# Mako_DSP_Power_R1_3.net
KiCad netlist of a schematic drawn in Altium Designer
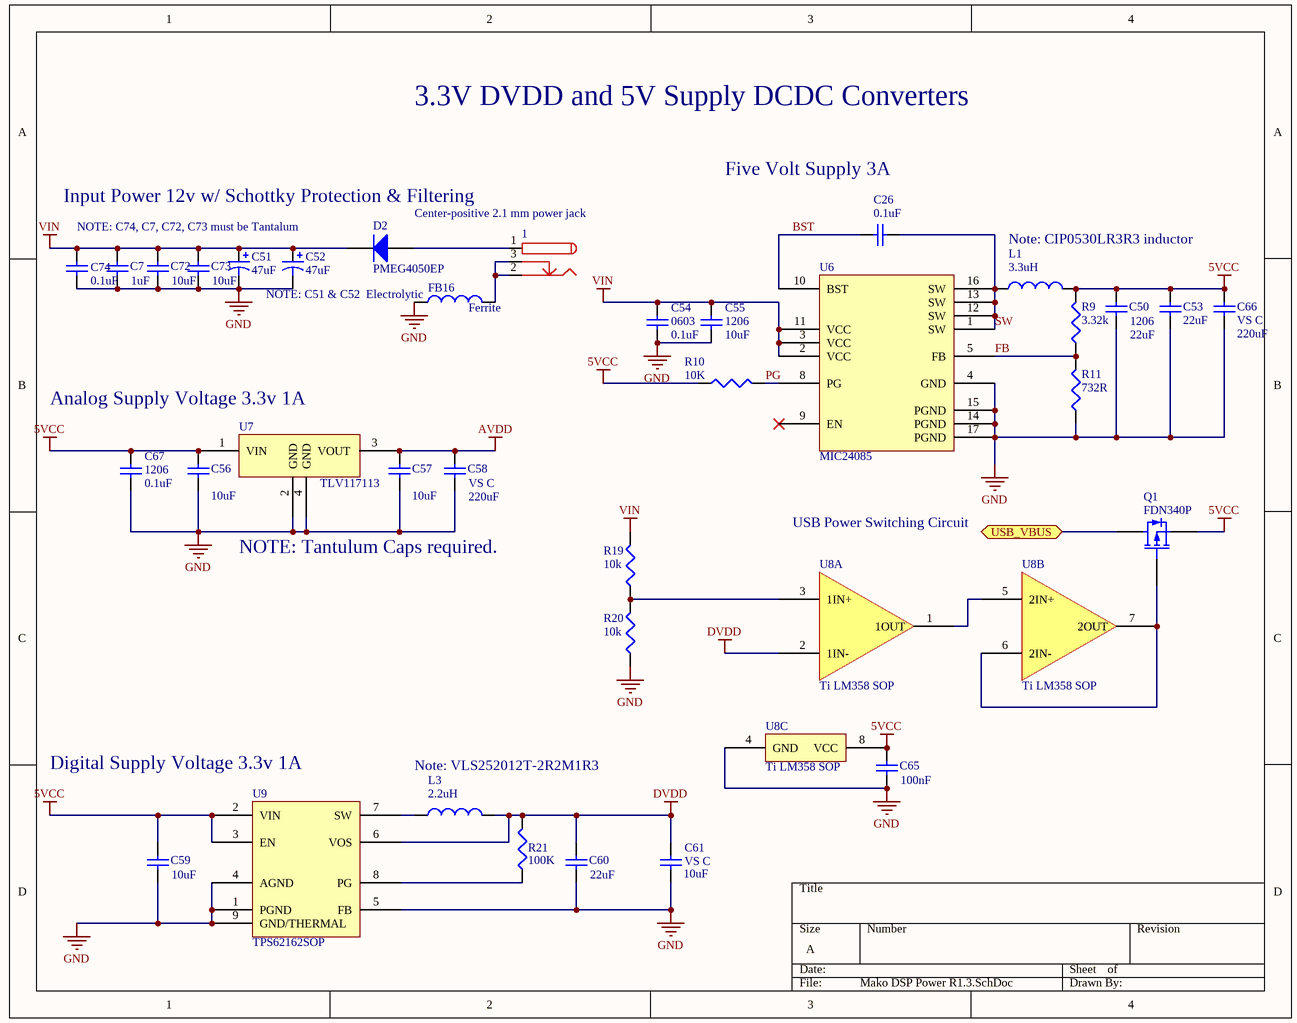
[diagram p0: Mako DSP Power R1.3.SchDoc]

(export (version "E")
  (design (tool "Eeschema 10.0.6"))
  (components
    (comp (ref "1")
      (value "Center-positive 2.1 mm power jack")
      (footprint "PJ-102AH")
      (description "Power jack")
      (fields (field (name "PUBLISHER") "Altium Limited"))
      (libsource (lib "Rascal") (part "PWR2.5"))
    )
    (comp (ref "C7")
      (value "1uF")
      (footprint "C1206")
      (description "Capacitor (Semiconductor SIM Model)")
      (fields (field (name "Comment") "Cap Semi") (field (name "PUBLISHER") "Altium Limited"))
      (libsource (lib "Miscellaneous Devices") (part "Cap Semi"))
    )
    (comp (ref "C26")
      (value "0.1uF")
      (footprint "1608[0603]")
      (description "Capacitor (Semiconductor SIM Model)")
      (fields (field (name "Comment") "Cap Semi") (field (name "PUBLISHER") "Altium Limited"))
      (libsource (lib "Miscellaneous Devices") (part "Cap Semi"))
    )
    (comp (ref "C50")
      (value "1206")
      (footprint "C1206")
      (description "Capacitor (Semiconductor SIM Model)")
      (fields (field (name "ALTIUM_VALUE") "22uF") (field (name "PUBLISHER") "Altium Limited"))
      (libsource (lib "Miscellaneous Devices") (part "Cap Semi"))
    )
    (comp (ref "C51")
      (value "47uF")
      (footprint "CAPPR2.5-6.3x5")
      (description "Polarized Capacitor (Radial)")
      (fields (field (name "Comment") "Cap Pol1") (field (name "PUBLISHER") "Altium Limited"))
      (libsource (lib "Miscellaneous Devices") (part "Cap Pol1"))
    )
    (comp (ref "C52")
      (value "47uF")
      (footprint "CAPPR2.5-6.3x5")
      (description "Polarized Capacitor (Radial)")
      (fields (field (name "Comment") "Cap Pol1") (field (name "PUBLISHER") "Altium Limited"))
      (libsource (lib "Miscellaneous Devices") (part "Cap Pol1"))
    )
    (comp (ref "C53")
      (value "22uF")
      (footprint "C1206")
      (description "Capacitor (Semiconductor SIM Model)")
      (fields (field (name "Comment") "Cap Semi") (field (name "PUBLISHER") "Altium Limited"))
      (libsource (lib "Miscellaneous Devices") (part "Cap Semi"))
    )
    (comp (ref "C54")
      (value "0603")
      (footprint "1608[0603]")
      (description "Capacitor (Semiconductor SIM Model)")
      (fields (field (name "ALTIUM_VALUE") "0.1uF") (field (name "PUBLISHER") "Altium Limited"))
      (libsource (lib "Miscellaneous Devices") (part "Cap Semi"))
    )
    (comp (ref "C55")
      (value "1206")
      (footprint "C1206")
      (description "Capacitor (Semiconductor SIM Model)")
      (fields (field (name "ALTIUM_VALUE") "10uF") (field (name "PUBLISHER") "Altium Limited"))
      (libsource (lib "Miscellaneous Devices") (part "Cap Semi"))
    )
    (comp (ref "C56")
      (value "10uF")
      (footprint "C1206")
      (description "Capacitor (Semiconductor SIM Model)")
      (fields (field (name "Comment") "Cap Semi") (field (name "PUBLISHER") "Altium Limited"))
      (libsource (lib "Miscellaneous Devices") (part "Cap Semi"))
    )
    (comp (ref "C57")
      (value "10uF")
      (footprint "C1206")
      (description "Capacitor (Semiconductor SIM Model)")
      (fields (field (name "Comment") "Cap Semi") (field (name "PUBLISHER") "Altium Limited"))
      (libsource (lib "Miscellaneous Devices") (part "Cap Semi"))
    )
    (comp (ref "C58")
      (value "VS C")
      (footprint "Panasonic VS C")
      (description "Capacitor (Semiconductor SIM Model)")
      (fields (field (name "ALTIUM_VALUE") "220uF") (field (name "PUBLISHER") "Altium Limited"))
      (libsource (lib "Miscellaneous Devices") (part "Cap Semi"))
    )
    (comp (ref "C59")
      (value "10uF")
      (footprint "C1206")
      (description "Capacitor (Semiconductor SIM Model)")
      (fields (field (name "Comment") "Cap Semi") (field (name "PUBLISHER") "Altium Limited"))
      (libsource (lib "Miscellaneous Devices") (part "Cap Semi"))
    )
    (comp (ref "C60")
      (value "22uF")
      (footprint "C1206")
      (description "Capacitor (Semiconductor SIM Model)")
      (fields (field (name "Comment") "Cap Semi") (field (name "PUBLISHER") "Altium Limited"))
      (libsource (lib "Miscellaneous Devices") (part "Cap Semi"))
    )
    (comp (ref "C61")
      (value "VS C")
      (footprint "Panasonic VS C")
      (description "Capacitor (Semiconductor SIM Model)")
      (fields (field (name "ALTIUM_VALUE") "10uF") (field (name "PUBLISHER") "Altium Limited"))
      (libsource (lib "Miscellaneous Devices") (part "Cap Semi"))
    )
    (comp (ref "C65")
      (value "100nF")
      (footprint "1608[0603]")
      (description "Capacitor (Semiconductor SIM Model)")
      (fields (field (name "Comment") "Cap Semi") (field (name "PUBLISHER") "Altium Limited"))
      (libsource (lib "Miscellaneous Devices") (part "Cap Semi"))
    )
    (comp (ref "C66")
      (value "VS C")
      (footprint "Panasonic VS C")
      (description "Capacitor (Semiconductor SIM Model)")
      (fields (field (name "ALTIUM_VALUE") "220uF") (field (name "PUBLISHER") "Altium Limited"))
      (libsource (lib "Miscellaneous Devices") (part "Cap Semi"))
    )
    (comp (ref "C67")
      (value "1206")
      (footprint "C1206")
      (description "Capacitor (Semiconductor SIM Model)")
      (fields (field (name "ALTIUM_VALUE") "0.1uF") (field (name "PUBLISHER") "Altium Limited"))
      (libsource (lib "Miscellaneous Devices") (part "Cap Semi"))
    )
    (comp (ref "C72")
      (value "10uF")
      (footprint "C1206")
      (description "Capacitor (Semiconductor SIM Model)")
      (fields (field (name "Comment") "Cap Semi") (field (name "PUBLISHER") "Altium Limited"))
      (libsource (lib "Miscellaneous Devices") (part "Cap Semi"))
    )
    (comp (ref "C73")
      (value "10uF")
      (footprint "C1206")
      (description "Capacitor (Semiconductor SIM Model)")
      (fields (field (name "Comment") "Cap Semi") (field (name "PUBLISHER") "Altium Limited"))
      (libsource (lib "Miscellaneous Devices") (part "Cap Semi"))
    )
    (comp (ref "C74")
      (value "0.1uF")
      (footprint "C1206")
      (description "Capacitor (Semiconductor SIM Model)")
      (fields (field (name "Comment") "Cap Semi") (field (name "PUBLISHER") "Altium Limited"))
      (libsource (lib "Miscellaneous Devices") (part "Cap Semi"))
    )
    (comp (ref "D2")
      (value "PMEG4050EP")
      (footprint "PMEG4050EP")
      (description "Default Diode")
      (fields (field (name "PUBLISHER") "Altium Limited"))
      (libsource (lib "Miscellaneous Devices") (part "Diode"))
    )
    (comp (ref "FB16")
      (value "Ferrite")
      (footprint "SM 0805 - gap trimmed")
      (description "Inductor")
      (fields (field (name "PUBLISHER") "Altium Limited"))
      (libsource (lib "Miscellaneous Devices") (part "Inductor"))
    )
    (comp (ref "L1")
      (value "3.3uH")
      (footprint "CIP0530LR3R3")
      (description "Inductor")
      (fields (field (name "PUBLISHER") "Altium Limited"))
      (libsource (lib "Miscellaneous Devices") (part "Inductor"))
    )
    (comp (ref "L3")
      (value "2.2uH")
      (footprint "VLS252012T-2R2M1R3")
      (description "Inductor")
      (fields (field (name "PUBLISHER") "Altium Limited"))
      (libsource (lib "Miscellaneous Devices") (part "Inductor"))
    )
    (comp (ref "Q1")
      (value "FDN340P")
      (footprint "SOT23-3N")
      (description "P-Channel MOSFET")
      (fields (field (name "PUBLISHER") "Altium Limited"))
      (libsource (lib "Mako DSP Schematic Library") (part "FDN340P"))
    )
    (comp (ref "R9")
      (value "3.32k")
      (footprint "J1-0603")
      (description "Resistor")
      (fields (field (name "Comment") "Res3") (field (name "PUBLISHER") "Altium Limited"))
      (libsource (lib "Miscellaneous Devices") (part "Res3"))
    )
    (comp (ref "R10")
      (value "10K")
      (footprint "J1-0603")
      (description "Resistor")
      (fields (field (name "Comment") "Res3") (field (name "PUBLISHER") "Altium Limited"))
      (libsource (lib "Miscellaneous Devices") (part "Res3"))
    )
    (comp (ref "R11")
      (value "732R")
      (footprint "J1-0603")
      (description "Resistor")
      (fields (field (name "Comment") "Res3") (field (name "PUBLISHER") "Altium Limited"))
      (libsource (lib "Miscellaneous Devices") (part "Res3"))
    )
    (comp (ref "R19")
      (value "10k")
      (footprint "J1-0603")
      (description "Resistor")
      (fields (field (name "Comment") "Res3") (field (name "PUBLISHER") "Altium Limited"))
      (libsource (lib "Miscellaneous Devices") (part "Res3"))
    )
    (comp (ref "R20")
      (value "10k")
      (footprint "J1-0603")
      (description "Resistor")
      (fields (field (name "Comment") "Res3") (field (name "PUBLISHER") "Altium Limited"))
      (libsource (lib "Miscellaneous Devices") (part "Res3"))
    )
    (comp (ref "R21")
      (value "100K")
      (footprint "RESC2012L")
      (description "Resistor")
      (fields (field (name "Comment") "Res3") (field (name "PUBLISHER") "Altium Limited"))
      (libsource (lib "Miscellaneous Devices") (part "Res3"))
    )
    (comp (ref "U6")
      (value "MIC24085")
      (footprint "MIC24085-AYML")
      (libsource (lib "Adams Altium Library") (part "MIC24085"))
    )
    (comp (ref "U7")
      (value "TLV117113")
      (footprint "TLV117112")
      (description "Linear Regulator")
      (libsource (lib "Adams Altium Library") (part "TLV117112"))
    )
    (comp (ref "U8")
      (value "Ti LM358 SOP")
      (footprint "LM358")
      (libsource (lib "Mako DSP Schematic Library") (part "LM358_Symbol"))
    )
    (comp (ref "U9")
      (value "TPS62162SOP")
      (footprint "TPS62162SOP")
      (libsource (lib "Adams Altium Library") (part "TPS62162SOP"))
    )
  )
  (nets
    (net (code "1") (name "/BST") (class "Default")
      (node (ref "C26") (pin "2") (pinfunction "2_2") (pintype "passive"))
      (node (ref "U6") (pin "10") (pinfunction "BST_10") (pintype "passive"))
    )
    (net (code "2") (name "/FB") (class "Default")
      (node (ref "R11") (pin "2") (pinfunction "2_2") (pintype "passive"))
      (node (ref "R9") (pin "1") (pinfunction "1_1") (pintype "passive"))
      (node (ref "U6") (pin "5") (pinfunction "FB_5") (pintype "passive"))
    )
    (net (code "3") (name "/PG") (class "Default")
      (node (ref "R10") (pin "2") (pinfunction "2_2") (pintype "passive"))
      (node (ref "U6") (pin "8") (pinfunction "PG_8") (pintype "passive"))
    )
    (net (code "4") (name "/SW") (class "Default")
      (node (ref "C26") (pin "1") (pinfunction "1_1") (pintype "passive"))
      (node (ref "L1") (pin "1") (pinfunction "1_1") (pintype "passive"))
      (node (ref "U6") (pin "1") (pinfunction "SW_1") (pintype "passive"))
      (node (ref "U6") (pin "12") (pinfunction "SW_12") (pintype "passive"))
      (node (ref "U6") (pin "13") (pinfunction "SW_13") (pintype "passive"))
      (node (ref "U6") (pin "16") (pinfunction "SW_16") (pintype "passive"))
    )
    (net (code "5") (name "/USB_VBUS") (class "Default")
      (node (ref "Q1") (pin "3") (pinfunction "S_3") (pintype "passive"))
    )
    (net (code "6") (name "5VCC") (class "Default")
      (node (ref "C50") (pin "2") (pinfunction "2_2") (pintype "passive"))
      (node (ref "C53") (pin "1") (pinfunction "1_1") (pintype "passive"))
      (node (ref "C56") (pin "1") (pinfunction "1_1") (pintype "passive"))
      (node (ref "C59") (pin "2") (pinfunction "2_2") (pintype "passive"))
      (node (ref "C65") (pin "1") (pinfunction "1_1") (pintype "passive"))
      (node (ref "C66") (pin "2") (pinfunction "2_2") (pintype "passive"))
      (node (ref "C67") (pin "2") (pinfunction "2_2") (pintype "passive"))
      (node (ref "L1") (pin "2") (pinfunction "2_2") (pintype "passive"))
      (node (ref "Q1") (pin "2") (pinfunction "D_2") (pintype "passive"))
      (node (ref "R10") (pin "1") (pinfunction "1_1") (pintype "passive"))
      (node (ref "R9") (pin "2") (pinfunction "2_2") (pintype "passive"))
      (node (ref "U7") (pin "1") (pinfunction "VIN_1") (pintype "passive"))
      (node (ref "U8") (pin "8") (pinfunction "VCC_8") (pintype "passive"))
      (node (ref "U9") (pin "2") (pinfunction "VIN_2") (pintype "passive"))
      (node (ref "U9") (pin "3") (pinfunction "EN_3") (pintype "passive"))
    )
    (net (code "7") (name "AVDD") (class "Default")
      (node (ref "C57") (pin "1") (pinfunction "1_1") (pintype "passive"))
      (node (ref "C58") (pin "1") (pinfunction "1_1") (pintype "passive"))
      (node (ref "U7") (pin "3") (pinfunction "VOUT_3") (pintype "passive"))
    )
    (net (code "8") (name "DVDD") (class "Default")
      (node (ref "C60") (pin "2") (pinfunction "2_2") (pintype "passive"))
      (node (ref "C61") (pin "1") (pinfunction "1_1") (pintype "passive"))
      (node (ref "L3") (pin "2") (pinfunction "2_2") (pintype "passive"))
      (node (ref "R21") (pin "2") (pinfunction "2_2") (pintype "passive"))
      (node (ref "U8") (pin "2") (pinfunction "1IN-_2") (pintype "passive"))
      (node (ref "U9") (pin "6") (pinfunction "VOS_6") (pintype "passive"))
    )
    (net (code "9") (name "GND") (class "Default")
      (node (ref "C50") (pin "1") (pinfunction "1_1") (pintype "passive"))
      (node (ref "C51") (pin "2") (pinfunction "2_2") (pintype "passive"))
      (node (ref "C52") (pin "2") (pinfunction "2_2") (pintype "passive"))
      (node (ref "C53") (pin "2") (pinfunction "2_2") (pintype "passive"))
      (node (ref "C54") (pin "1") (pinfunction "1_1") (pintype "passive"))
      (node (ref "C55") (pin "1") (pinfunction "1_1") (pintype "passive"))
      (node (ref "C56") (pin "2") (pinfunction "2_2") (pintype "passive"))
      (node (ref "C57") (pin "2") (pinfunction "2_2") (pintype "passive"))
      (node (ref "C58") (pin "2") (pinfunction "2_2") (pintype "passive"))
      (node (ref "C59") (pin "1") (pinfunction "1_1") (pintype "passive"))
      (node (ref "C60") (pin "1") (pinfunction "1_1") (pintype "passive"))
      (node (ref "C61") (pin "2") (pinfunction "2_2") (pintype "passive"))
      (node (ref "C65") (pin "2") (pinfunction "2_2") (pintype "passive"))
      (node (ref "C66") (pin "1") (pinfunction "1_1") (pintype "passive"))
      (node (ref "C67") (pin "1") (pinfunction "1_1") (pintype "passive"))
      (node (ref "C7") (pin "1") (pinfunction "1_1") (pintype "passive"))
      (node (ref "C72") (pin "1") (pinfunction "1_1") (pintype "passive"))
      (node (ref "C73") (pin "1") (pinfunction "1_1") (pintype "passive"))
      (node (ref "C74") (pin "1") (pinfunction "1_1") (pintype "passive"))
      (node (ref "FB16") (pin "1") (pinfunction "1_1") (pintype "passive"))
      (node (ref "R11") (pin "1") (pinfunction "1_1") (pintype "passive"))
      (node (ref "R20") (pin "1") (pinfunction "1_1") (pintype "passive"))
      (node (ref "U6") (pin "14") (pinfunction "PGND_14") (pintype "passive"))
      (node (ref "U6") (pin "15") (pinfunction "PGND_15") (pintype "passive"))
      (node (ref "U6") (pin "17") (pinfunction "PGND_17") (pintype "passive"))
      (node (ref "U6") (pin "4") (pinfunction "GND_4") (pintype "passive"))
      (node (ref "U7") (pin "2") (pinfunction "GND_2") (pintype "passive"))
      (node (ref "U7") (pin "4") (pinfunction "GND_4") (pintype "passive"))
      (node (ref "U8") (pin "4") (pinfunction "GND_4") (pintype "passive"))
      (node (ref "U9") (pin "1") (pinfunction "PGND_1") (pintype "passive"))
      (node (ref "U9") (pin "4") (pinfunction "AGND_4") (pintype "passive"))
      (node (ref "U9") (pin "5") (pinfunction "FB_5") (pintype "passive"))
      (node (ref "U9") (pin "9") (pinfunction "GND/THERMAL_9") (pintype "passive"))
    )
    (net (code "10") (name "Net-(1-Pad2)") (class "Default")
      (node (ref "1") (pin "2") (pinfunction "2_2") (pintype "power_in"))
      (node (ref "1") (pin "3") (pinfunction "3_3") (pintype "power_in"))
      (node (ref "FB16") (pin "2") (pinfunction "2_2") (pintype "passive"))
    )
    (net (code "11") (name "Net-(D2-K)") (class "Default")
      (node (ref "1") (pin "1") (pinfunction "1_1") (pintype "power_in"))
      (node (ref "D2") (pin "2") (pinfunction "K_2") (pintype "passive"))
    )
    (net (code "12") (name "Net-(Q1-G)") (class "Default")
      (node (ref "Q1") (pin "1") (pinfunction "G_1") (pintype "passive"))
      (node (ref "U8") (pin "6") (pinfunction "2IN-_6") (pintype "passive"))
      (node (ref "U8") (pin "7") (pinfunction "2OUT_7") (pintype "passive"))
    )
    (net (code "13") (name "Net-(U8A-1IN+)") (class "Default")
      (node (ref "R19") (pin "1") (pinfunction "1_1") (pintype "passive"))
      (node (ref "R20") (pin "2") (pinfunction "2_2") (pintype "passive"))
      (node (ref "U8") (pin "3") (pinfunction "1IN+_3") (pintype "passive"))
    )
    (net (code "14") (name "Net-(U8A-1OUT)") (class "Default")
      (node (ref "U8") (pin "1") (pinfunction "1OUT_1") (pintype "passive"))
      (node (ref "U8") (pin "5") (pinfunction "2IN+_5") (pintype "passive"))
    )
    (net (code "15") (name "Net-(U9-PG)") (class "Default")
      (node (ref "R21") (pin "1") (pinfunction "1_1") (pintype "passive"))
      (node (ref "U9") (pin "8") (pinfunction "PG_8") (pintype "passive"))
    )
    (net (code "16") (name "Net-(U9-SW)") (class "Default")
      (node (ref "L3") (pin "1") (pinfunction "1_1") (pintype "passive"))
      (node (ref "U9") (pin "7") (pinfunction "SW_7") (pintype "passive"))
    )
    (net (code "17") (name "VIN") (class "Default")
      (node (ref "C51") (pin "1") (pinfunction "1_1") (pintype "passive"))
      (node (ref "C52") (pin "1") (pinfunction "1_1") (pintype "passive"))
      (node (ref "C54") (pin "2") (pinfunction "2_2") (pintype "passive"))
      (node (ref "C55") (pin "2") (pinfunction "2_2") (pintype "passive"))
      (node (ref "C7") (pin "2") (pinfunction "2_2") (pintype "passive"))
      (node (ref "C72") (pin "2") (pinfunction "2_2") (pintype "passive"))
      (node (ref "C73") (pin "2") (pinfunction "2_2") (pintype "passive"))
      (node (ref "C74") (pin "2") (pinfunction "2_2") (pintype "passive"))
      (node (ref "D2") (pin "1") (pinfunction "A_1") (pintype "passive"))
      (node (ref "R19") (pin "2") (pinfunction "2_2") (pintype "passive"))
      (node (ref "U6") (pin "11") (pinfunction "VCC_11") (pintype "passive"))
      (node (ref "U6") (pin "2") (pinfunction "VCC_2") (pintype "passive"))
      (node (ref "U6") (pin "3") (pinfunction "VCC_3") (pintype "passive"))
    )
    (net (code "18") (name "unconnected-(U6-EN-Pad9)") (class "Default")
      (node (ref "U6") (pin "9") (pinfunction "EN_9") (pintype "passive+no_connect"))
    )
    (net (code "19") (name "unconnected-(U6-NC-Pad6)") (class "Default")
      (node (ref "U6") (pin "6") (pinfunction "NC_6") (pintype "passive"))
    )
    (net (code "20") (name "unconnected-(U6-NC-Pad7)") (class "Default")
      (node (ref "U6") (pin "7") (pinfunction "NC_7") (pintype "passive"))
    )
  )
)
